# tee_dweebo.net
KiCad netlist of a schematic drawn in EAGLE
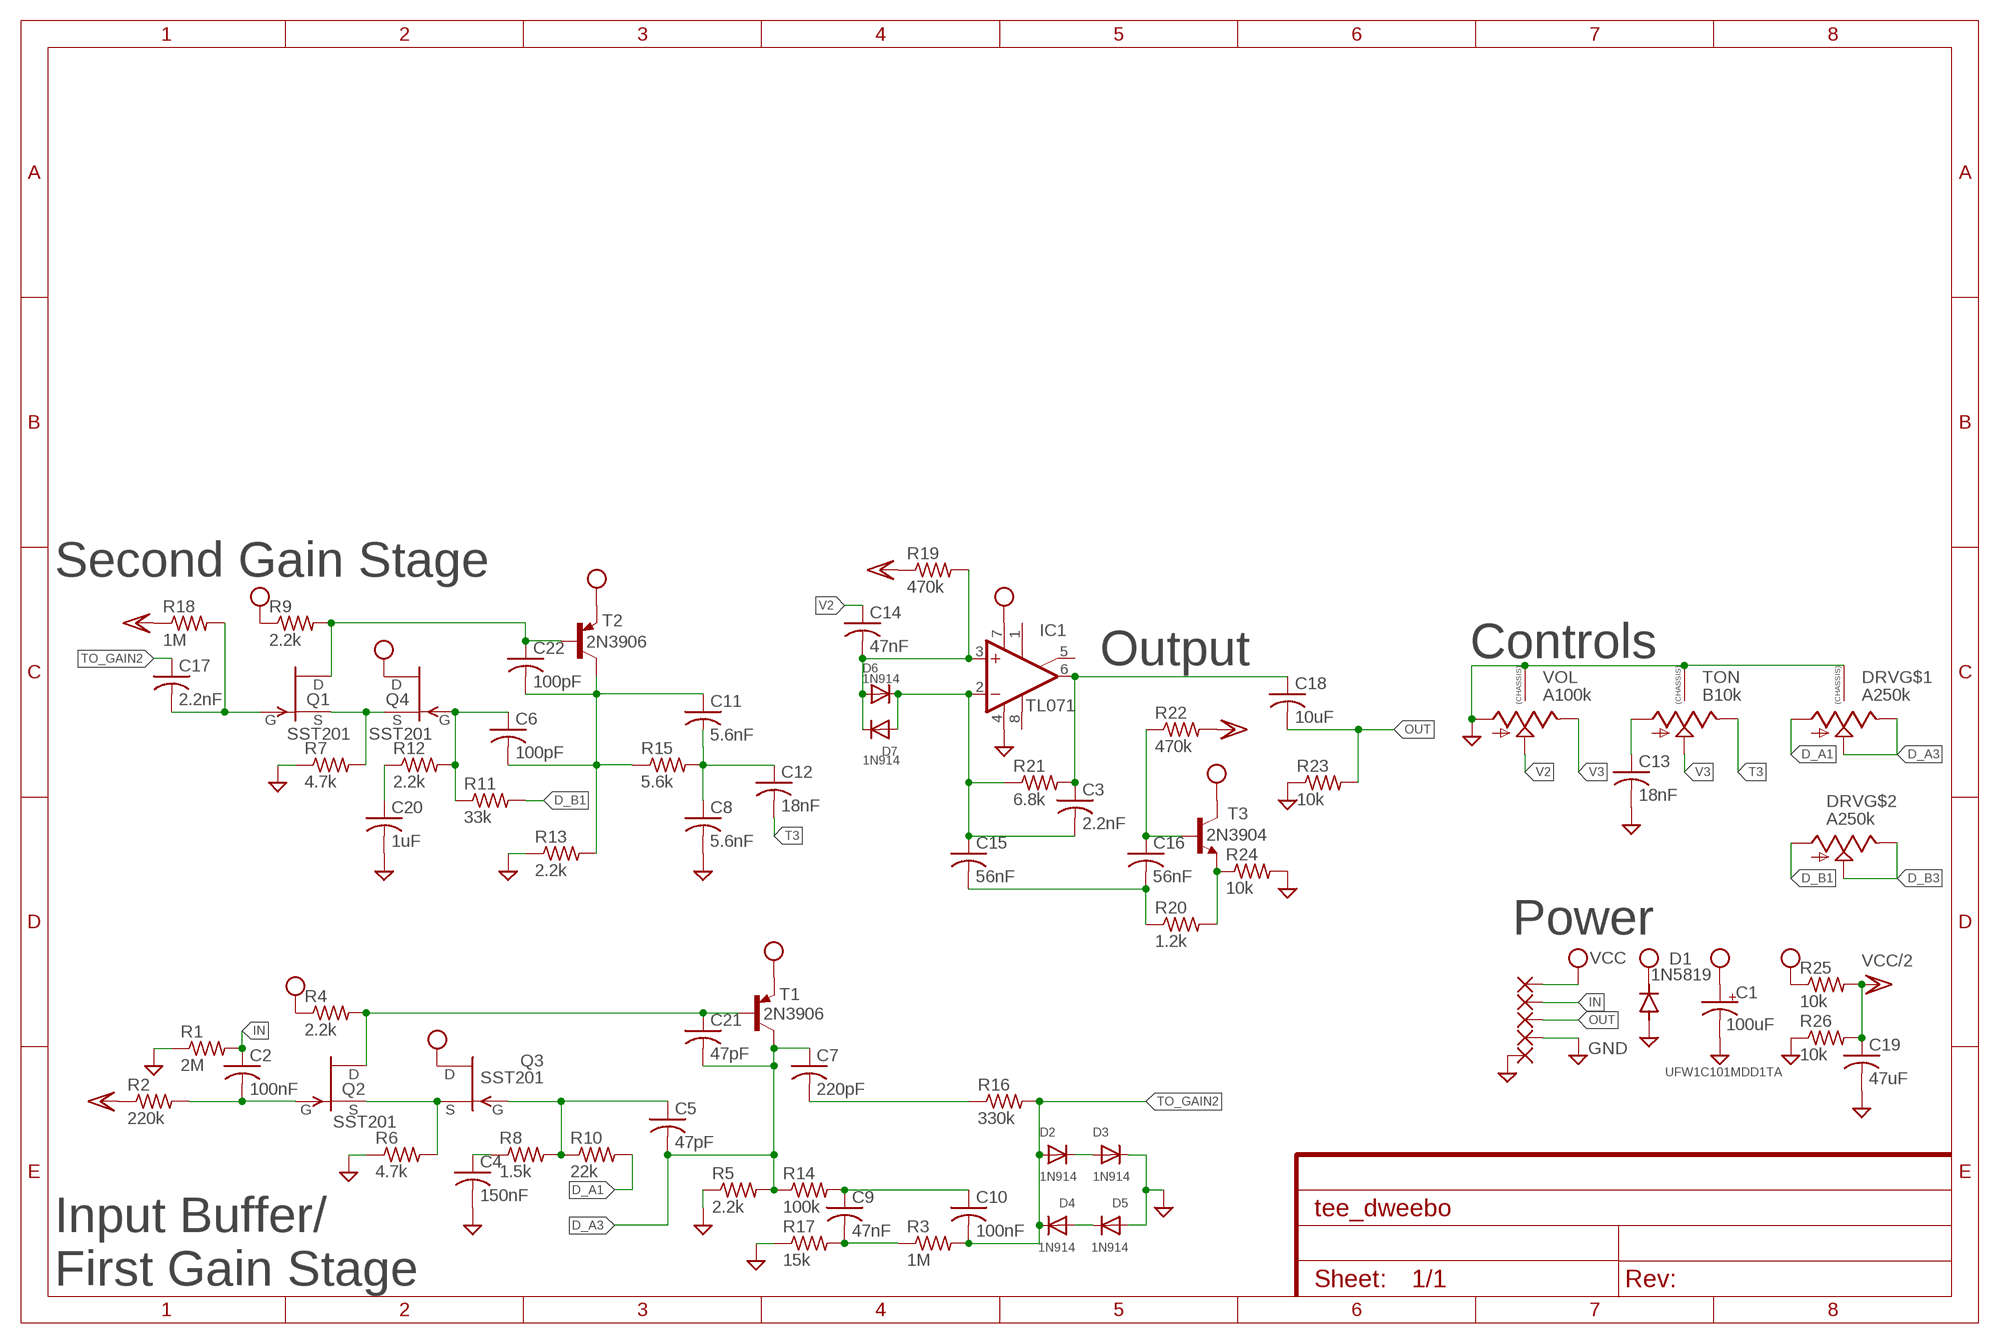
[diagram p0: schematic, sheet 1]

(export (version "E")
  (design (tool "Eeschema 10.0.6"))
  (components
    (comp (ref "C1")
      (value "100uF")
      (footprint "eagle-import:ELEC10UF_SM")
      (libsource (lib "eagle-import") (part "050_FLAT"))
    )
    (comp (ref "C2")
      (value "100nF")
      (footprint "eagle-import:C0402")
      (libsource (lib "eagle-import") (part "C-USC0402"))
    )
    (comp (ref "C3")
      (value "2.2nF")
      (footprint "eagle-import:C0402")
      (libsource (lib "eagle-import") (part "C-USC0402"))
    )
    (comp (ref "C4")
      (value "150nF")
      (footprint "eagle-import:C0402")
      (libsource (lib "eagle-import") (part "C-USC0402"))
    )
    (comp (ref "C5")
      (value "47pF")
      (footprint "eagle-import:C0402")
      (libsource (lib "eagle-import") (part "C-USC0402"))
    )
    (comp (ref "C6")
      (value "100pF")
      (footprint "eagle-import:C0402")
      (libsource (lib "eagle-import") (part "C-USC0402"))
    )
    (comp (ref "C7")
      (value "220pF")
      (footprint "eagle-import:C0402")
      (libsource (lib "eagle-import") (part "C-USC0402"))
    )
    (comp (ref "C8")
      (value "5.6nF")
      (footprint "eagle-import:C0402")
      (libsource (lib "eagle-import") (part "C-USC0402"))
    )
    (comp (ref "C9")
      (value "47nF")
      (footprint "eagle-import:C0402")
      (libsource (lib "eagle-import") (part "C-USC0402"))
    )
    (comp (ref "C10")
      (value "100nF")
      (footprint "eagle-import:C0402")
      (libsource (lib "eagle-import") (part "C-USC0402"))
    )
    (comp (ref "C11")
      (value "5.6nF")
      (footprint "eagle-import:C0402")
      (libsource (lib "eagle-import") (part "C-USC0402"))
    )
    (comp (ref "C12")
      (value "18nF")
      (footprint "eagle-import:C0402")
      (libsource (lib "eagle-import") (part "C-USC0402"))
    )
    (comp (ref "C13")
      (value "18nF")
      (footprint "eagle-import:C0402")
      (libsource (lib "eagle-import") (part "C-USC0402"))
    )
    (comp (ref "C14")
      (value "47nF")
      (footprint "eagle-import:C0402")
      (libsource (lib "eagle-import") (part "C-USC0402"))
    )
    (comp (ref "C15")
      (value "56nF")
      (footprint "eagle-import:C0402")
      (libsource (lib "eagle-import") (part "C-USC0402"))
    )
    (comp (ref "C16")
      (value "56nF")
      (footprint "eagle-import:C0402")
      (libsource (lib "eagle-import") (part "C-USC0402"))
    )
    (comp (ref "C17")
      (value "2.2nF")
      (footprint "eagle-import:C0402")
      (libsource (lib "eagle-import") (part "C-USC0402"))
    )
    (comp (ref "C18")
      (value "10uF")
      (footprint "eagle-import:C0805")
      (libsource (lib "eagle-import") (part "C-USC0805"))
    )
    (comp (ref "C19")
      (value "47uF")
      (footprint "eagle-import:C1206")
      (libsource (lib "eagle-import") (part "C-USC1206"))
    )
    (comp (ref "C20")
      (value "1uF")
      (footprint "eagle-import:C0603")
      (libsource (lib "eagle-import") (part "adafruit_420_C-USC0603"))
    )
    (comp (ref "C21")
      (value "47pF")
      (footprint "eagle-import:C0402")
      (libsource (lib "eagle-import") (part "C-USC0402"))
    )
    (comp (ref "C22")
      (value "100pF")
      (footprint "eagle-import:C0402")
      (libsource (lib "eagle-import") (part "C-USC0402"))
    )
    (comp (ref "D1")
      (value "1N5819")
      (footprint "eagle-import:SOD123")
      (libsource (lib "eagle-import") (part "DIODE-SOD123"))
    )
    (comp (ref "D2")
      (value "1N914")
      (footprint "eagle-import:SOD-323F")
      (libsource (lib "eagle-import") (part "DIODESOD-323F"))
    )
    (comp (ref "D3")
      (value "1N914")
      (footprint "eagle-import:SOD-323F")
      (libsource (lib "eagle-import") (part "DIODESOD-323F"))
    )
    (comp (ref "D4")
      (value "1N914")
      (footprint "eagle-import:SOD-323F")
      (libsource (lib "eagle-import") (part "DIODESOD-323F"))
    )
    (comp (ref "D5")
      (value "1N914")
      (footprint "eagle-import:SOD-323F")
      (libsource (lib "eagle-import") (part "DIODESOD-323F"))
    )
    (comp (ref "D6")
      (value "1N914")
      (footprint "eagle-import:SOD-323F")
      (libsource (lib "eagle-import") (part "DIODESOD-323F"))
    )
    (comp (ref "D7")
      (value "1N914")
      (footprint "eagle-import:SOD-323F")
      (libsource (lib "eagle-import") (part "DIODESOD-323F"))
    )
    (comp (ref "DRV")
      (value "A250k")
      (footprint "eagle-import:DUAL_9MM_SNAP-IN_POT")
      (libsource (lib "eagle-import") (part "ALPHA-9MM-DUALPOT"))
    )
    (comp (ref "IC1")
      (value "TL071")
      (footprint "eagle-import:SO08")
      (libsource (lib "eagle-import") (part "TL071D"))
    )
    (comp (ref "PAD1")
      (value "1,6/0,8")
      (footprint "eagle-import:1,6_0,8")
      (libsource (lib "eagle-import") (part "1,6/0,8"))
    )
    (comp (ref "PAD2")
      (value "1,6/0,8")
      (footprint "eagle-import:1,6_0,8")
      (libsource (lib "eagle-import") (part "1,6/0,8"))
    )
    (comp (ref "PAD3")
      (value "1,6/0,8")
      (footprint "eagle-import:1,6_0,8")
      (libsource (lib "eagle-import") (part "1,6/0,8"))
    )
    (comp (ref "PAD4")
      (value "1,6/0,8")
      (footprint "eagle-import:1,6_0,8")
      (libsource (lib "eagle-import") (part "1,6/0,8"))
    )
    (comp (ref "PAD5")
      (value "1,6/0,8")
      (footprint "eagle-import:1,6_0,8")
      (libsource (lib "eagle-import") (part "1,6/0,8"))
    )
    (comp (ref "Q1")
      (value "SST201")
      (footprint "eagle-import:SOT23")
      (libsource (lib "eagle-import") (part "?20SST1"))
    )
    (comp (ref "Q2")
      (value "SST201")
      (footprint "eagle-import:SOT23")
      (libsource (lib "eagle-import") (part "?20SST1"))
    )
    (comp (ref "Q3")
      (value "SST201")
      (footprint "eagle-import:SOT23")
      (libsource (lib "eagle-import") (part "?20SST1"))
    )
    (comp (ref "Q4")
      (value "SST201")
      (footprint "eagle-import:SOT23")
      (libsource (lib "eagle-import") (part "?20SST1"))
    )
    (comp (ref "R1")
      (value "2M")
      (footprint "eagle-import:R0402")
      (libsource (lib "eagle-import") (part "R-US_R0402"))
    )
    (comp (ref "R2")
      (value "220k")
      (footprint "eagle-import:R0402")
      (libsource (lib "eagle-import") (part "R-US_R0402"))
    )
    (comp (ref "R3")
      (value "1M")
      (footprint "eagle-import:R0402")
      (libsource (lib "eagle-import") (part "R-US_R0402"))
    )
    (comp (ref "R4")
      (value "2.2k")
      (footprint "eagle-import:R0402")
      (libsource (lib "eagle-import") (part "R-US_R0402"))
    )
    (comp (ref "R5")
      (value "2.2k")
      (footprint "eagle-import:R0402")
      (libsource (lib "eagle-import") (part "R-US_R0402"))
    )
    (comp (ref "R6")
      (value "4.7k")
      (footprint "eagle-import:R0402")
      (libsource (lib "eagle-import") (part "R-US_R0402"))
    )
    (comp (ref "R7")
      (value "4.7k")
      (footprint "eagle-import:R0402")
      (libsource (lib "eagle-import") (part "R-US_R0402"))
    )
    (comp (ref "R8")
      (value "1.5k")
      (footprint "eagle-import:R0402")
      (libsource (lib "eagle-import") (part "R-US_R0402"))
    )
    (comp (ref "R9")
      (value "2.2k")
      (footprint "eagle-import:R0402")
      (libsource (lib "eagle-import") (part "R-US_R0402"))
    )
    (comp (ref "R10")
      (value "22k")
      (footprint "eagle-import:R0402")
      (libsource (lib "eagle-import") (part "R-US_R0402"))
    )
    (comp (ref "R11")
      (value "33k")
      (footprint "eagle-import:R0402")
      (libsource (lib "eagle-import") (part "R-US_R0402"))
    )
    (comp (ref "R12")
      (value "2.2k")
      (footprint "eagle-import:R0402")
      (libsource (lib "eagle-import") (part "R-US_R0402"))
    )
    (comp (ref "R13")
      (value "2.2k")
      (footprint "eagle-import:R0402")
      (libsource (lib "eagle-import") (part "R-US_R0402"))
    )
    (comp (ref "R14")
      (value "100k")
      (footprint "eagle-import:R0402")
      (libsource (lib "eagle-import") (part "R-US_R0402"))
    )
    (comp (ref "R15")
      (value "5.6k")
      (footprint "eagle-import:R0402")
      (libsource (lib "eagle-import") (part "R-US_R0402"))
    )
    (comp (ref "R16")
      (value "330k")
      (footprint "eagle-import:R0402")
      (libsource (lib "eagle-import") (part "R-US_R0402"))
    )
    (comp (ref "R17")
      (value "15k")
      (footprint "eagle-import:R0402")
      (libsource (lib "eagle-import") (part "R-US_R0402"))
    )
    (comp (ref "R18")
      (value "1M")
      (footprint "eagle-import:R0402")
      (libsource (lib "eagle-import") (part "R-US_R0402"))
    )
    (comp (ref "R19")
      (value "470k")
      (footprint "eagle-import:R0402")
      (libsource (lib "eagle-import") (part "R-US_R0402"))
    )
    (comp (ref "R20")
      (value "1.2k")
      (footprint "eagle-import:R0402")
      (libsource (lib "eagle-import") (part "R-US_R0402"))
    )
    (comp (ref "R21")
      (value "6.8k")
      (footprint "eagle-import:R0402")
      (libsource (lib "eagle-import") (part "R-US_R0402"))
    )
    (comp (ref "R22")
      (value "470k")
      (footprint "eagle-import:R0402")
      (libsource (lib "eagle-import") (part "R-US_R0402"))
    )
    (comp (ref "R23")
      (value "10k")
      (footprint "eagle-import:R0402")
      (libsource (lib "eagle-import") (part "R-US_R0402"))
    )
    (comp (ref "R24")
      (value "10k")
      (footprint "eagle-import:R0402")
      (libsource (lib "eagle-import") (part "R-US_R0402"))
    )
    (comp (ref "R25")
      (value "10k")
      (footprint "eagle-import:R0402")
      (libsource (lib "eagle-import") (part "R-US_R0402"))
    )
    (comp (ref "R26")
      (value "10k")
      (footprint "eagle-import:R0402")
      (libsource (lib "eagle-import") (part "R-US_R0402"))
    )
    (comp (ref "T1")
      (value "2N3906")
      (footprint "eagle-import:SOT23-BEC")
      (libsource (lib "eagle-import") (part "-PNP-SOT23-BECMMBT3906LT1"))
    )
    (comp (ref "T2")
      (value "2N3906")
      (footprint "eagle-import:SOT23-BEC")
      (libsource (lib "eagle-import") (part "-PNP-SOT23-BECMMBT3906LT1"))
    )
    (comp (ref "T3")
      (value "2N3904")
      (footprint "eagle-import:SOT23-BEC")
      (libsource (lib "eagle-import") (part "-NPN-SOT23-BECMMBT3904LT1"))
    )
    (comp (ref "TON")
      (value "B10k")
      (footprint "eagle-import:9MM_SNAP-IN_POT")
      (libsource (lib "eagle-import") (part "9MM_SNAP-IN_POT_CHASSIS"))
    )
    (comp (ref "VOL")
      (value "A100k")
      (footprint "eagle-import:9MM_SNAP-IN_POT")
      (libsource (lib "eagle-import") (part "9MM_SNAP-IN_POT_CHASSIS"))
    )
  )
  (nets
    (net (code "1") (name "D_A1") (class "Default")
      (node (ref "DRV") (pin "1") (pinfunction "A_1") (pintype "passive"))
      (node (ref "R10") (pin "2") (pinfunction "2_2") (pintype "passive"))
    )
    (net (code "2") (name "D_A3") (class "Default")
      (node (ref "C21") (pin "2") (pinfunction "2_2") (pintype "passive"))
      (node (ref "C5") (pin "2") (pinfunction "2_2") (pintype "passive"))
      (node (ref "C7") (pin "1") (pinfunction "1_1") (pintype "passive"))
      (node (ref "DRV") (pin "2") (pinfunction "S_2") (pintype "passive"))
      (node (ref "DRV") (pin "3") (pinfunction "E_3") (pintype "passive"))
      (node (ref "R14") (pin "1") (pinfunction "1_1") (pintype "passive"))
      (node (ref "R5") (pin "2") (pinfunction "2_2") (pintype "passive"))
      (node (ref "T1") (pin "C") (pinfunction "C_C") (pintype "passive"))
    )
    (net (code "3") (name "D_B1") (class "Default")
      (node (ref "DRV") (pin "1B") (pinfunction "A_1B") (pintype "passive"))
      (node (ref "R11") (pin "2") (pinfunction "2_2") (pintype "passive"))
    )
    (net (code "4") (name "D_B3") (class "Default")
      (node (ref "DRV") (pin "2B") (pinfunction "S_2B") (pintype "passive"))
      (node (ref "DRV") (pin "3B") (pinfunction "E_3B") (pintype "passive"))
    )
    (net (code "5") (name "GND") (class "Default")
      (node (ref "C1") (pin "-") (pinfunction "-_-") (pintype "passive"))
      (node (ref "C13") (pin "2") (pinfunction "2_2") (pintype "passive"))
      (node (ref "C19") (pin "2") (pinfunction "2_2") (pintype "passive"))
      (node (ref "C20") (pin "2") (pinfunction "2_2") (pintype "passive"))
      (node (ref "C4") (pin "2") (pinfunction "2_2") (pintype "passive"))
      (node (ref "C8") (pin "2") (pinfunction "2_2") (pintype "passive"))
      (node (ref "D1") (pin "A") (pinfunction "A_A") (pintype "passive"))
      (node (ref "D3") (pin "C") (pinfunction "C_C") (pintype "passive"))
      (node (ref "D5") (pin "A") (pinfunction "A_A") (pintype "passive"))
      (node (ref "DRV") (pin "CHASSIS1") (pinfunction "P$1_CHASSIS1") (pintype "passive"))
      (node (ref "DRV") (pin "CHASSIS2") (pinfunction "P$1_CHASSIS2") (pintype "passive"))
      (node (ref "IC1") (pin "4") (pinfunction "V-_4") (pintype "power_in"))
      (node (ref "PAD4") (pin "1") (pinfunction "P_1") (pintype "passive"))
      (node (ref "PAD5") (pin "1") (pinfunction "P_1") (pintype "passive"))
      (node (ref "R1") (pin "1") (pinfunction "1_1") (pintype "passive"))
      (node (ref "R13") (pin "1") (pinfunction "1_1") (pintype "passive"))
      (node (ref "R17") (pin "1") (pinfunction "1_1") (pintype "passive"))
      (node (ref "R23") (pin "1") (pinfunction "1_1") (pintype "passive"))
      (node (ref "R24") (pin "2") (pinfunction "2_2") (pintype "passive"))
      (node (ref "R26") (pin "1") (pinfunction "1_1") (pintype "passive"))
      (node (ref "R5") (pin "1") (pinfunction "1_1") (pintype "passive"))
      (node (ref "R6") (pin "1") (pinfunction "1_1") (pintype "passive"))
      (node (ref "R7") (pin "1") (pinfunction "1_1") (pintype "passive"))
      (node (ref "TON") (pin "CHASSIS1") (pinfunction "P$1_CHASSIS1") (pintype "passive"))
      (node (ref "TON") (pin "CHASSIS2") (pinfunction "P$1_CHASSIS2") (pintype "passive"))
      (node (ref "VOL") (pin "1") (pinfunction "A_1") (pintype "passive"))
      (node (ref "VOL") (pin "CHASSIS1") (pinfunction "P$1_CHASSIS1") (pintype "passive"))
      (node (ref "VOL") (pin "CHASSIS2") (pinfunction "P$1_CHASSIS2") (pintype "passive"))
    )
    (net (code "6") (name "IN") (class "Default")
      (node (ref "C2") (pin "1") (pinfunction "1_1") (pintype "passive"))
      (node (ref "PAD2") (pin "1") (pinfunction "P_1") (pintype "passive"))
      (node (ref "R1") (pin "2") (pinfunction "2_2") (pintype "passive"))
    )
    (net (code "7") (name "Net-(C4-Pad1)") (class "Default")
      (node (ref "C4") (pin "1") (pinfunction "1_1") (pintype "passive"))
      (node (ref "R8") (pin "1") (pinfunction "1_1") (pintype "passive"))
    )
    (net (code "8") (name "Net-(C7-Pad2)") (class "Default")
      (node (ref "C7") (pin "2") (pinfunction "2_2") (pintype "passive"))
      (node (ref "R16") (pin "1") (pinfunction "1_1") (pintype "passive"))
    )
    (net (code "9") (name "Net-(C9-Pad2)") (class "Default")
      (node (ref "C9") (pin "2") (pinfunction "2_2") (pintype "passive"))
      (node (ref "R17") (pin "2") (pinfunction "2_2") (pintype "passive"))
      (node (ref "R3") (pin "1") (pinfunction "1_1") (pintype "passive"))
    )
    (net (code "10") (name "Net-(C10-Pad1)") (class "Default")
      (node (ref "C10") (pin "1") (pinfunction "1_1") (pintype "passive"))
      (node (ref "C9") (pin "1") (pinfunction "1_1") (pintype "passive"))
      (node (ref "R14") (pin "2") (pinfunction "2_2") (pintype "passive"))
    )
    (net (code "11") (name "Net-(C11-Pad1)") (class "Default")
      (node (ref "C11") (pin "1") (pinfunction "1_1") (pintype "passive"))
      (node (ref "C22") (pin "2") (pinfunction "2_2") (pintype "passive"))
      (node (ref "C6") (pin "2") (pinfunction "2_2") (pintype "passive"))
      (node (ref "R13") (pin "2") (pinfunction "2_2") (pintype "passive"))
      (node (ref "R15") (pin "1") (pinfunction "1_1") (pintype "passive"))
      (node (ref "T2") (pin "C") (pinfunction "C_C") (pintype "passive"))
    )
    (net (code "12") (name "Net-(C11-Pad2)") (class "Default")
      (node (ref "C11") (pin "2") (pinfunction "2_2") (pintype "passive"))
      (node (ref "C12") (pin "1") (pinfunction "1_1") (pintype "passive"))
      (node (ref "C8") (pin "1") (pinfunction "1_1") (pintype "passive"))
      (node (ref "R15") (pin "2") (pinfunction "2_2") (pintype "passive"))
    )
    (net (code "13") (name "Net-(C15-Pad2)") (class "Default")
      (node (ref "C15") (pin "2") (pinfunction "2_2") (pintype "passive"))
      (node (ref "C16") (pin "2") (pinfunction "2_2") (pintype "passive"))
      (node (ref "R20") (pin "1") (pinfunction "1_1") (pintype "passive"))
    )
    (net (code "14") (name "Net-(C16-Pad1)") (class "Default")
      (node (ref "C16") (pin "1") (pinfunction "1_1") (pintype "passive"))
      (node (ref "R22") (pin "1") (pinfunction "1_1") (pintype "passive"))
      (node (ref "T3") (pin "B") (pinfunction "B_B") (pintype "passive"))
    )
    (net (code "15") (name "Net-(C20-Pad1)") (class "Default")
      (node (ref "C20") (pin "1") (pinfunction "1_1") (pintype "passive"))
      (node (ref "R12") (pin "1") (pinfunction "1_1") (pintype "passive"))
    )
    (net (code "16") (name "Net-(D2-PadC)") (class "Default")
      (node (ref "D2") (pin "C") (pinfunction "C_C") (pintype "passive"))
      (node (ref "D3") (pin "A") (pinfunction "A_A") (pintype "passive"))
    )
    (net (code "17") (name "Net-(D4-PadA)") (class "Default")
      (node (ref "D4") (pin "A") (pinfunction "A_A") (pintype "passive"))
      (node (ref "D5") (pin "C") (pinfunction "C_C") (pintype "passive"))
    )
    (net (code "18") (name "Net-(IC1-+IN)") (class "Default")
      (node (ref "C14") (pin "2") (pinfunction "2_2") (pintype "passive"))
      (node (ref "D6") (pin "A") (pinfunction "A_A") (pintype "passive"))
      (node (ref "D7") (pin "C") (pinfunction "C_C") (pintype "passive"))
      (node (ref "IC1") (pin "3") (pinfunction "+IN_3") (pintype "input"))
      (node (ref "R19") (pin "2") (pinfunction "2_2") (pintype "passive"))
    )
    (net (code "19") (name "Net-(IC1--IN)") (class "Default")
      (node (ref "C15") (pin "1") (pinfunction "1_1") (pintype "passive"))
      (node (ref "C3") (pin "2") (pinfunction "2_2") (pintype "passive"))
      (node (ref "D6") (pin "C") (pinfunction "C_C") (pintype "passive"))
      (node (ref "D7") (pin "A") (pinfunction "A_A") (pintype "passive"))
      (node (ref "IC1") (pin "2") (pinfunction "-IN_2") (pintype "input"))
      (node (ref "R21") (pin "1") (pinfunction "1_1") (pintype "passive"))
    )
    (net (code "20") (name "Net-(IC1-OUT)") (class "Default")
      (node (ref "C18") (pin "1") (pinfunction "1_1") (pintype "passive"))
      (node (ref "C3") (pin "1") (pinfunction "1_1") (pintype "passive"))
      (node (ref "IC1") (pin "6") (pinfunction "OUT_6") (pintype "output"))
      (node (ref "R21") (pin "2") (pinfunction "2_2") (pintype "passive"))
    )
    (net (code "21") (name "Net-(Q1-D)") (class "Default")
      (node (ref "C22") (pin "1") (pinfunction "1_1") (pintype "passive"))
      (node (ref "Q1") (pin "1") (pinfunction "D_1") (pintype "passive"))
      (node (ref "R9") (pin "2") (pinfunction "2_2") (pintype "passive"))
      (node (ref "T2") (pin "B") (pinfunction "B_B") (pintype "passive"))
    )
    (net (code "22") (name "Net-(Q1-G)") (class "Default")
      (node (ref "C17") (pin "2") (pinfunction "2_2") (pintype "passive"))
      (node (ref "Q1") (pin "3") (pinfunction "G_3") (pintype "passive"))
      (node (ref "R18") (pin "2") (pinfunction "2_2") (pintype "passive"))
    )
    (net (code "23") (name "Net-(Q1-S)") (class "Default")
      (node (ref "Q1") (pin "2") (pinfunction "S_2") (pintype "passive"))
      (node (ref "Q4") (pin "2") (pinfunction "S_2") (pintype "passive"))
      (node (ref "R7") (pin "2") (pinfunction "2_2") (pintype "passive"))
    )
    (net (code "24") (name "Net-(Q2-D)") (class "Default")
      (node (ref "C21") (pin "1") (pinfunction "1_1") (pintype "passive"))
      (node (ref "Q2") (pin "1") (pinfunction "D_1") (pintype "passive"))
      (node (ref "R4") (pin "2") (pinfunction "2_2") (pintype "passive"))
      (node (ref "T1") (pin "B") (pinfunction "B_B") (pintype "passive"))
    )
    (net (code "25") (name "Net-(Q2-G)") (class "Default")
      (node (ref "C2") (pin "2") (pinfunction "2_2") (pintype "passive"))
      (node (ref "Q2") (pin "3") (pinfunction "G_3") (pintype "passive"))
      (node (ref "R2") (pin "2") (pinfunction "2_2") (pintype "passive"))
    )
    (net (code "26") (name "Net-(Q2-S)") (class "Default")
      (node (ref "Q2") (pin "2") (pinfunction "S_2") (pintype "passive"))
      (node (ref "Q3") (pin "2") (pinfunction "S_2") (pintype "passive"))
      (node (ref "R6") (pin "2") (pinfunction "2_2") (pintype "passive"))
    )
    (net (code "27") (name "Net-(Q3-G)") (class "Default")
      (node (ref "C5") (pin "1") (pinfunction "1_1") (pintype "passive"))
      (node (ref "Q3") (pin "3") (pinfunction "G_3") (pintype "passive"))
      (node (ref "R10") (pin "1") (pinfunction "1_1") (pintype "passive"))
      (node (ref "R8") (pin "2") (pinfunction "2_2") (pintype "passive"))
    )
    (net (code "28") (name "Net-(Q4-G)") (class "Default")
      (node (ref "C6") (pin "1") (pinfunction "1_1") (pintype "passive"))
      (node (ref "Q4") (pin "3") (pinfunction "G_3") (pintype "passive"))
      (node (ref "R11") (pin "1") (pinfunction "1_1") (pintype "passive"))
      (node (ref "R12") (pin "2") (pinfunction "2_2") (pintype "passive"))
    )
    (net (code "29") (name "Net-(R20-Pad2)") (class "Default")
      (node (ref "R20") (pin "2") (pinfunction "2_2") (pintype "passive"))
      (node (ref "R24") (pin "1") (pinfunction "1_1") (pintype "passive"))
      (node (ref "T3") (pin "E") (pinfunction "E_E") (pintype "passive"))
    )
    (net (code "30") (name "Net-(TON-A)") (class "Default")
      (node (ref "C13") (pin "1") (pinfunction "1_1") (pintype "passive"))
      (node (ref "TON") (pin "1") (pinfunction "A_1") (pintype "passive"))
    )
    (net (code "31") (name "OUT") (class "Default")
      (node (ref "C18") (pin "2") (pinfunction "2_2") (pintype "passive"))
      (node (ref "PAD3") (pin "1") (pinfunction "P_1") (pintype "passive"))
      (node (ref "R23") (pin "2") (pinfunction "2_2") (pintype "passive"))
    )
    (net (code "32") (name "T3") (class "Default")
      (node (ref "C12") (pin "2") (pinfunction "2_2") (pintype "passive"))
      (node (ref "TON") (pin "3") (pinfunction "E_3") (pintype "passive"))
    )
    (net (code "33") (name "TO_GAIN2") (class "Default")
      (node (ref "C10") (pin "2") (pinfunction "2_2") (pintype "passive"))
      (node (ref "C17") (pin "1") (pinfunction "1_1") (pintype "passive"))
      (node (ref "D2") (pin "A") (pinfunction "A_A") (pintype "passive"))
      (node (ref "D4") (pin "C") (pinfunction "C_C") (pintype "passive"))
      (node (ref "R16") (pin "2") (pinfunction "2_2") (pintype "passive"))
      (node (ref "R3") (pin "2") (pinfunction "2_2") (pintype "passive"))
    )
    (net (code "34") (name "V2") (class "Default")
      (node (ref "C14") (pin "1") (pinfunction "1_1") (pintype "passive"))
      (node (ref "VOL") (pin "2") (pinfunction "S_2") (pintype "passive"))
    )
    (net (code "35") (name "V3") (class "Default")
      (node (ref "TON") (pin "2") (pinfunction "S_2") (pintype "passive"))
      (node (ref "VOL") (pin "3") (pinfunction "E_3") (pintype "passive"))
    )
    (net (code "36") (name "VCC") (class "Default")
      (node (ref "C1") (pin "+") (pinfunction "+_+") (pintype "passive"))
      (node (ref "D1") (pin "C") (pinfunction "C_C") (pintype "passive"))
      (node (ref "IC1") (pin "7") (pinfunction "V+_7") (pintype "power_in"))
      (node (ref "PAD1") (pin "1") (pinfunction "P_1") (pintype "passive"))
      (node (ref "Q3") (pin "1") (pinfunction "D_1") (pintype "passive"))
      (node (ref "Q4") (pin "1") (pinfunction "D_1") (pintype "passive"))
      (node (ref "R25") (pin "1") (pinfunction "1_1") (pintype "passive"))
      (node (ref "R4") (pin "1") (pinfunction "1_1") (pintype "passive"))
      (node (ref "R9") (pin "1") (pinfunction "1_1") (pintype "passive"))
      (node (ref "T1") (pin "E") (pinfunction "E_E") (pintype "passive"))
      (node (ref "T2") (pin "E") (pinfunction "E_E") (pintype "passive"))
      (node (ref "T3") (pin "C") (pinfunction "C_C") (pintype "passive"))
    )
    (net (code "37") (name "VCC{slash}2") (class "Default")
      (node (ref "C19") (pin "1") (pinfunction "1_1") (pintype "passive"))
      (node (ref "R18") (pin "1") (pinfunction "1_1") (pintype "passive"))
      (node (ref "R19") (pin "1") (pinfunction "1_1") (pintype "passive"))
      (node (ref "R2") (pin "1") (pinfunction "1_1") (pintype "passive"))
      (node (ref "R22") (pin "2") (pinfunction "2_2") (pintype "passive"))
      (node (ref "R25") (pin "2") (pinfunction "2_2") (pintype "passive"))
      (node (ref "R26") (pin "2") (pinfunction "2_2") (pintype "passive"))
    )
    (net (code "38") (name "unconnected-(IC1-ON1-Pad1)") (class "Default")
      (node (ref "IC1") (pin "1") (pinfunction "ON1_1") (pintype "passive"))
    )
    (net (code "39") (name "unconnected-(IC1-ON2-Pad5)") (class "Default")
      (node (ref "IC1") (pin "5") (pinfunction "ON2_5") (pintype "passive"))
    )
    (net (code "40") (name "unconnected-(IC1-OPT-Pad8)") (class "Default")
      (node (ref "IC1") (pin "8") (pinfunction "OPT_8") (pintype "passive"))
    )
  )
)
